# Sheet3.net
KiCad netlist of a schematic drawn in Altium Designer
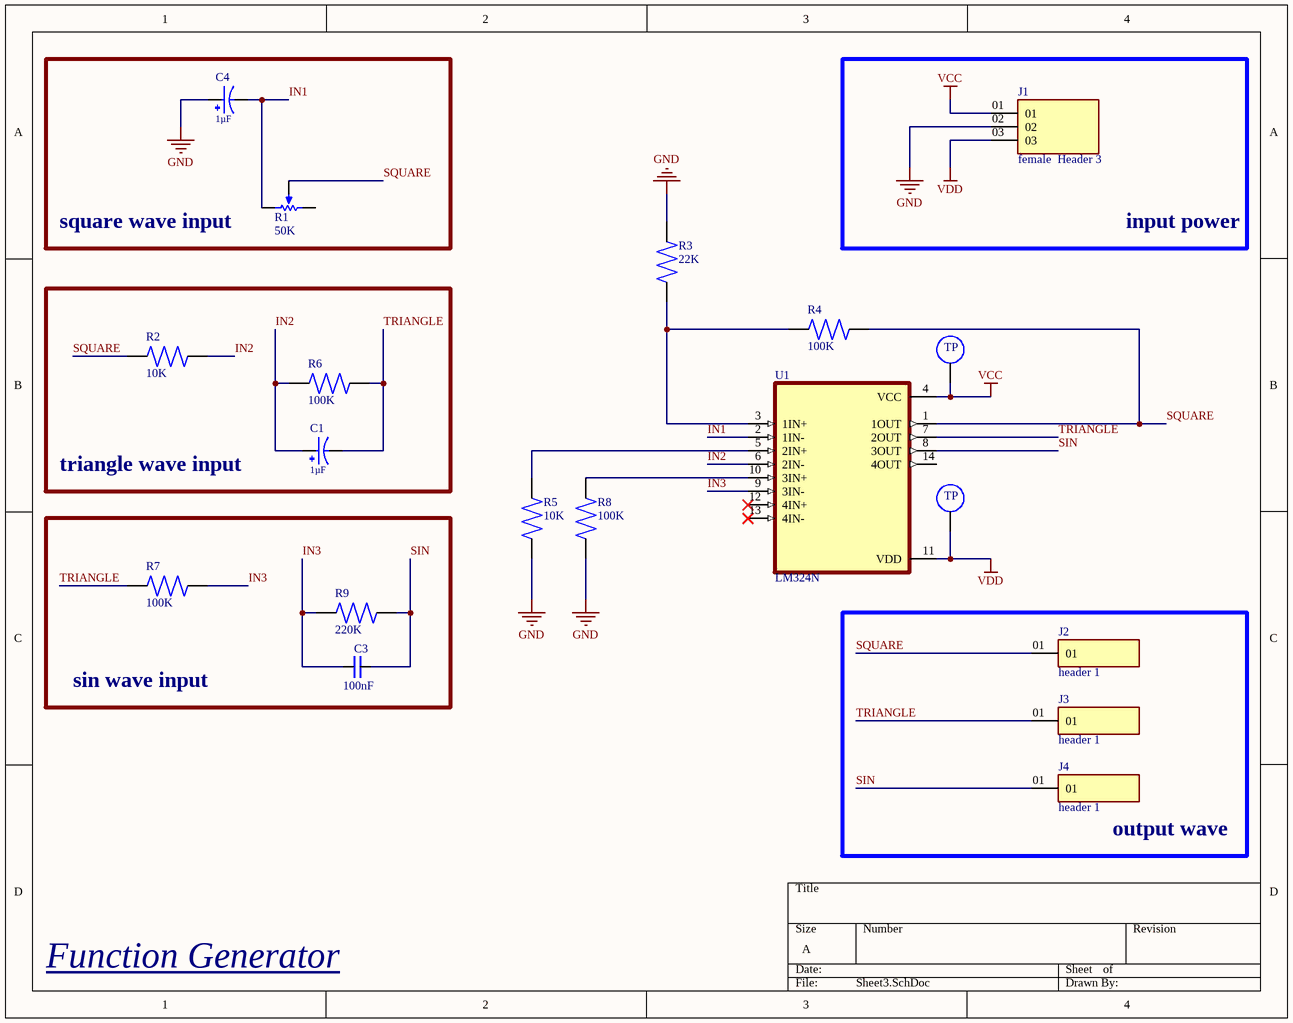
[diagram p0: Sheet3.SchDoc]

(export (version "E")
  (design (tool "Eeschema 10.0.6"))
  (components
    (comp (ref "C1")
      (value "1µF")
      (footprint "CAPPRD500W50D500H1100")
      (description "Cap Aluminum Lytic 1uF 50V 20% (5 X 11mm) Radial 5mm 10mA 1000h 105Â°C Automotive Ammo")
      (fields (field (name "MF") "Panasonic") (field (name "MP") "EEUHD1H1R0B"))
      (libsource (lib "project_Sch") (part "EEUHD1H1R0B"))
    )
    (comp (ref "C3")
      (value "100nF")
      (footprint "CAPRR254W50L508T317H508")
      (description "Capacitor, Ceramic, 100nF, 100VDC, 10-% Tol, 10+% Tol, X7R-TC Code, -15, 15%-TC")
      (fields (field (name "MF") "AVX") (field (name "MP") "SR291C104KARTR1"))
      (libsource (lib "project_Sch") (part "SR291C104KARTR1"))
    )
    (comp (ref "C4")
      (value "1µF")
      (footprint "CAPPRD500W50D500H1100")
      (description "Cap Aluminum Lytic 1uF 50V 20% (5 X 11mm) Radial 5mm 10mA 1000h 105Â°C Automotive Ammo")
      (fields (field (name "MF") "Panasonic") (field (name "MP") "EEUHD1H1R0B"))
      (libsource (lib "project_Sch") (part "EEUHD1H1R0B"))
    )
    (comp (ref "J1")
      (value "female  Header 3")
      (footprint "SAMTEC_TSW-103-19-S-S")
      (fields (field (name "MP") "TSW-103-19-S-S"))
      (libsource (lib "project_Sch") (part "TSW-103-19-S-S"))
    )
    (comp (ref "J2")
      (value "header 1")
      (footprint "SAMTEC_TMS-101-60-S-S")
      (fields (field (name "MP") "TMS-101-60-S-S"))
      (libsource (lib "project_Sch") (part "TMS-101-60-S-S"))
    )
    (comp (ref "J3")
      (value "header 1")
      (footprint "SAMTEC_TMS-101-60-S-S")
      (fields (field (name "MP") "TMS-101-60-S-S"))
      (libsource (lib "project_Sch") (part "TMS-101-60-S-S"))
    )
    (comp (ref "J4")
      (value "header 1")
      (footprint "SAMTEC_TMS-101-60-S-S")
      (fields (field (name "MP") "TMS-101-60-S-S"))
      (libsource (lib "project_Sch") (part "TMS-101-60-S-S"))
    )
    (comp (ref "R1")
      (value "50K")
      (footprint "33262M trimpot")
      (description "3362M Timpot")
      (fields (field (name "Comment") "3362 trimpot") (field (name "PUBLISHER") "Altium Limited"))
      (libsource (lib "project_Sch") (part "3362 trimpot"))
    )
    (comp (ref "R2")
      (value "10K")
      (footprint "RESAD1081W64L635D269")
      (description "RES 100K OHM 1/8W 1% AXIAL")
      (fields (field (name "MP") "RNC55H1003FMB14") (field (name "MF") "Vishay Dale"))
      (libsource (lib "project_Sch") (part "RNC55H1003FMB14"))
    )
    (comp (ref "R3")
      (value "22K")
      (footprint "RESAD1081W64L635D269")
      (description "RES 100K OHM 1/8W 1% AXIAL")
      (fields (field (name "MP") "RNC55H1003FMB14") (field (name "MF") "Vishay Dale"))
      (libsource (lib "project_Sch") (part "RNC55H1003FMB14"))
    )
    (comp (ref "R4")
      (value "100K")
      (footprint "RESAD1081W64L635D269")
      (description "RES 100K OHM 1/8W 1% AXIAL")
      (fields (field (name "MP") "RNC55H1003FMB14") (field (name "MF") "Vishay Dale"))
      (libsource (lib "project_Sch") (part "RNC55H1003FMB14"))
    )
    (comp (ref "R5")
      (value "10K")
      (footprint "RESAD1081W64L635D269")
      (description "RES 100K OHM 1/8W 1% AXIAL")
      (fields (field (name "MP") "RNC55H1003FMB14") (field (name "MF") "Vishay Dale"))
      (libsource (lib "project_Sch") (part "RNC55H1003FMB14"))
    )
    (comp (ref "R6")
      (value "100K")
      (footprint "RESAD1081W64L635D269")
      (description "RES 100K OHM 1/8W 1% AXIAL")
      (fields (field (name "MP") "RNC55H1003FMB14") (field (name "MF") "Vishay Dale"))
      (libsource (lib "project_Sch") (part "RNC55H1003FMB14"))
    )
    (comp (ref "R7")
      (value "100K")
      (footprint "RESAD1081W64L635D269")
      (description "RES 100K OHM 1/8W 1% AXIAL")
      (fields (field (name "MP") "RNC55H1003FMB14") (field (name "MF") "Vishay Dale"))
      (libsource (lib "project_Sch") (part "RNC55H1003FMB14"))
    )
    (comp (ref "R8")
      (value "100K")
      (footprint "RESAD1081W64L635D269")
      (description "RES 100K OHM 1/8W 1% AXIAL")
      (fields (field (name "MP") "RNC55H1003FMB14") (field (name "MF") "Vishay Dale"))
      (libsource (lib "project_Sch") (part "RNC55H1003FMB14"))
    )
    (comp (ref "R9")
      (value "220K")
      (footprint "RESAD1081W64L635D269")
      (description "RES 100K OHM 1/8W 1% AXIAL")
      (fields (field (name "MP") "RNC55H1003FMB14") (field (name "MF") "Vishay Dale"))
      (libsource (lib "project_Sch") (part "RNC55H1003FMB14"))
    )
    (comp (ref "U1")
      (value "LM324N")
      (footprint "DIP794W45P254L1969H508Q14")
      (description "General Purpose Amplifier 4 Circuit - 14-MDIP")
      (fields (field (name "MF") "ON Semiconductor"))
      (libsource (lib "project_Sch") (part "LM324N"))
    )
    (comp (ref "VCC")
      (value "TEST POINT")
      (footprint "TEST POINT")
      (libsource (lib "project_Sch") (part "TEST POINT"))
    )
    (comp (ref "VDD")
      (value "TEST POINT")
      (footprint "TEST POINT")
      (libsource (lib "project_Sch") (part "TEST POINT"))
    )
  )
  (nets
    (net (code "1") (name "/IN1") (class "Default")
      (node (ref "C4") (pin "N") (pinfunction "N_N") (pintype "passive"))
      (node (ref "R1") (pin "2") (pinfunction "BOT_2") (pintype "passive"))
      (node (ref "U1") (pin "2") (pinfunction "1IN-_2") (pintype "input"))
    )
    (net (code "2") (name "/IN2") (class "Default")
      (node (ref "C1") (pin "P") (pinfunction "P_P") (pintype "passive"))
      (node (ref "R2") (pin "2") (pinfunction "2_2") (pintype "passive"))
      (node (ref "R6") (pin "2") (pinfunction "2_2") (pintype "passive"))
      (node (ref "U1") (pin "6") (pinfunction "2IN-_6") (pintype "input"))
    )
    (net (code "3") (name "/IN3") (class "Default")
      (node (ref "C3") (pin "1") (pinfunction "1_1") (pintype "passive"))
      (node (ref "R7") (pin "2") (pinfunction "2_2") (pintype "passive"))
      (node (ref "R9") (pin "1") (pinfunction "1_1") (pintype "passive"))
      (node (ref "U1") (pin "9") (pinfunction "3IN-_9") (pintype "input"))
    )
    (net (code "4") (name "/SIN") (class "Default")
      (node (ref "C3") (pin "2") (pinfunction "2_2") (pintype "passive"))
      (node (ref "J4") (pin "01") (pinfunction "01_01") (pintype "passive"))
      (node (ref "R9") (pin "2") (pinfunction "2_2") (pintype "passive"))
      (node (ref "U1") (pin "8") (pinfunction "3OUT_8") (pintype "output"))
    )
    (net (code "5") (name "/SQUARE") (class "Default")
      (node (ref "J2") (pin "01") (pinfunction "01_01") (pintype "passive"))
      (node (ref "R1") (pin "3") (pinfunction "TAP_3") (pintype "passive"))
      (node (ref "R2") (pin "1") (pinfunction "1_1") (pintype "passive"))
      (node (ref "R4") (pin "2") (pinfunction "2_2") (pintype "passive"))
      (node (ref "U1") (pin "1") (pinfunction "1OUT_1") (pintype "output"))
    )
    (net (code "6") (name "/TRIANGLE") (class "Default")
      (node (ref "C1") (pin "N") (pinfunction "N_N") (pintype "passive"))
      (node (ref "J3") (pin "01") (pinfunction "01_01") (pintype "passive"))
      (node (ref "R6") (pin "1") (pinfunction "1_1") (pintype "passive"))
      (node (ref "R7") (pin "1") (pinfunction "1_1") (pintype "passive"))
      (node (ref "U1") (pin "7") (pinfunction "2OUT_7") (pintype "output"))
    )
    (net (code "7") (name "GND") (class "Default")
      (node (ref "C4") (pin "P") (pinfunction "P_P") (pintype "passive"))
      (node (ref "J1") (pin "02") (pinfunction "02_02") (pintype "passive"))
      (node (ref "R3") (pin "2") (pinfunction "2_2") (pintype "passive"))
      (node (ref "R5") (pin "1") (pinfunction "1_1") (pintype "passive"))
      (node (ref "R8") (pin "1") (pinfunction "1_1") (pintype "passive"))
    )
    (net (code "8") (name "Net-(U1-1IN+)") (class "Default")
      (node (ref "R3") (pin "1") (pinfunction "1_1") (pintype "passive"))
      (node (ref "R4") (pin "1") (pinfunction "1_1") (pintype "passive"))
      (node (ref "U1") (pin "3") (pinfunction "1IN+_3") (pintype "input"))
    )
    (net (code "9") (name "Net-(U1-2IN+)") (class "Default")
      (node (ref "R5") (pin "2") (pinfunction "2_2") (pintype "passive"))
      (node (ref "U1") (pin "5") (pinfunction "2IN+_5") (pintype "input"))
    )
    (net (code "10") (name "Net-(U1-3IN+)") (class "Default")
      (node (ref "R8") (pin "2") (pinfunction "2_2") (pintype "passive"))
      (node (ref "U1") (pin "10") (pinfunction "3IN+_10") (pintype "input"))
    )
    (net (code "11") (name "VCC") (class "Default")
      (node (ref "J1") (pin "01") (pinfunction "01_01") (pintype "passive"))
      (node (ref "U1") (pin "4") (pinfunction "VCC_4") (pintype "power_in"))
      (node (ref "VCC") (pin "1") (pinfunction "1_1") (pintype "passive"))
    )
    (net (code "12") (name "VDD") (class "Default")
      (node (ref "J1") (pin "03") (pinfunction "03_03") (pintype "passive"))
      (node (ref "U1") (pin "11") (pinfunction "VDD_11") (pintype "power_in"))
      (node (ref "VDD") (pin "1") (pinfunction "1_1") (pintype "passive"))
    )
    (net (code "13") (name "unconnected-(R1-TOP-Pad1)") (class "Default")
      (node (ref "R1") (pin "1") (pinfunction "TOP_1") (pintype "passive"))
    )
    (net (code "14") (name "unconnected-(U1-4IN+-Pad12)") (class "Default")
      (node (ref "U1") (pin "12") (pinfunction "4IN+_12") (pintype "input+no_connect"))
    )
    (net (code "15") (name "unconnected-(U1-4IN--Pad13)") (class "Default")
      (node (ref "U1") (pin "13") (pinfunction "4IN-_13") (pintype "input+no_connect"))
    )
    (net (code "16") (name "unconnected-(U1-4OUT-Pad14)") (class "Default")
      (node (ref "U1") (pin "14") (pinfunction "4OUT_14") (pintype "output"))
    )
  )
)
